# Teensy-Maxuino-Master.net
KiCad netlist of a schematic drawn in EAGLE
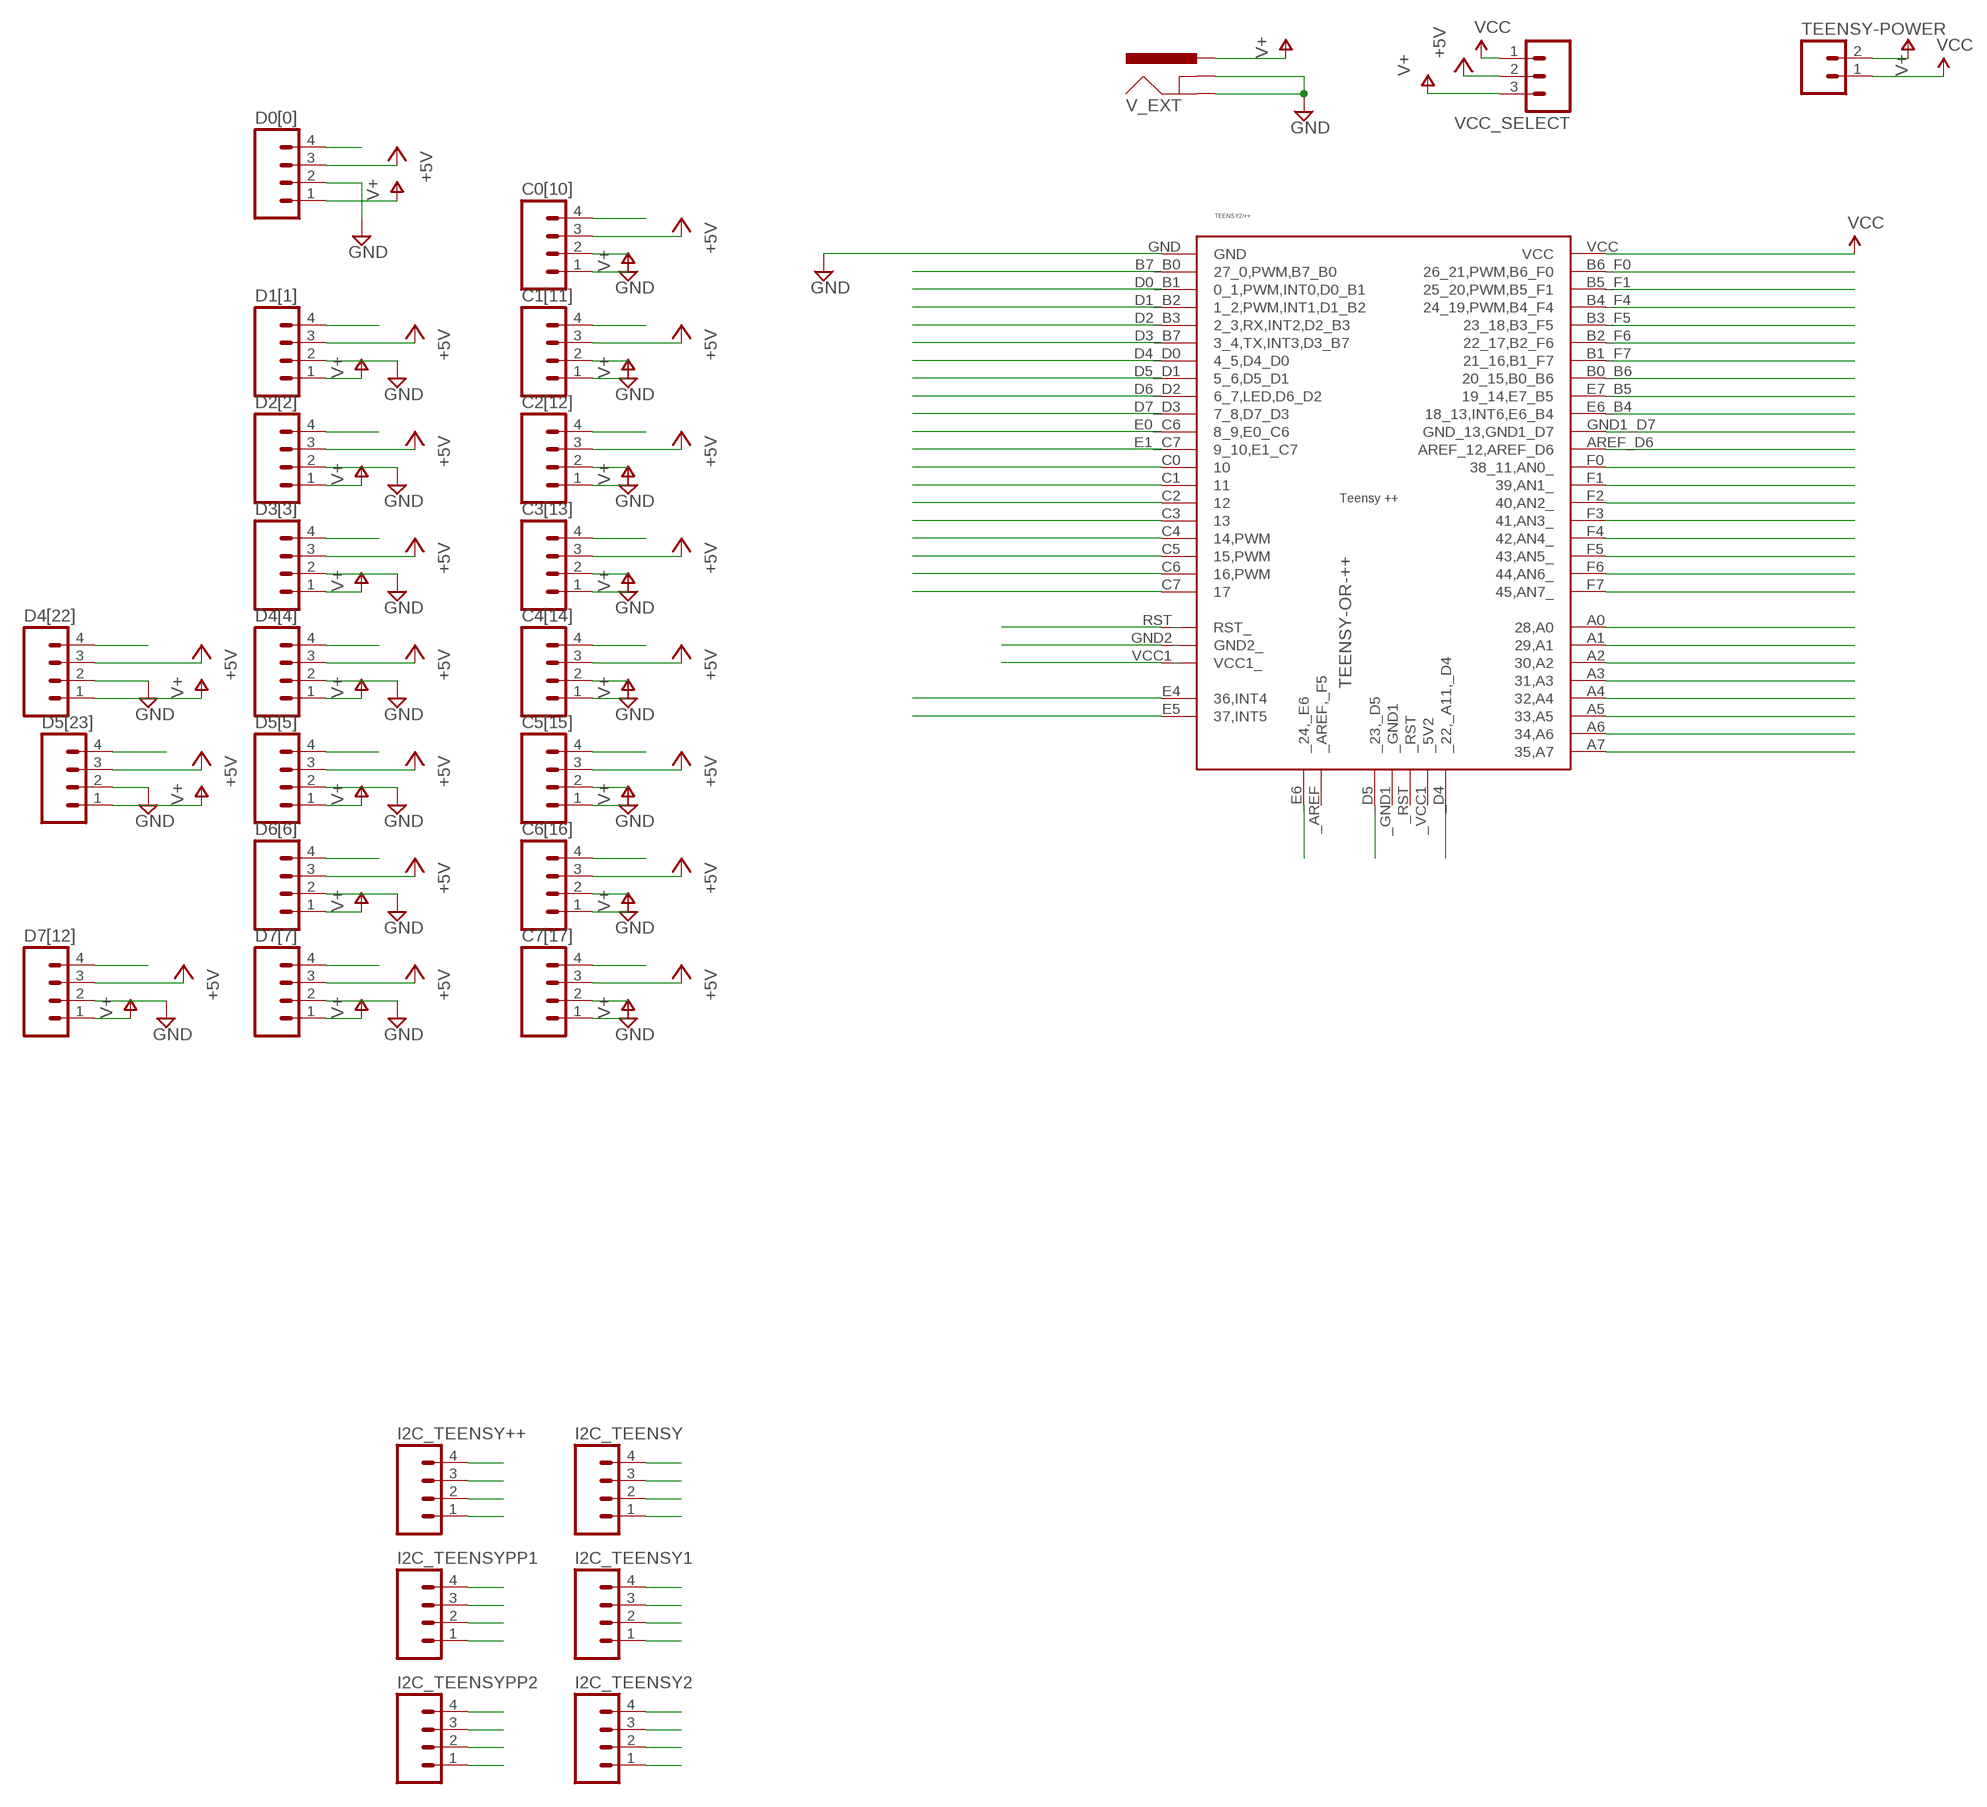
[diagram p0: schematic, sheet 1, part 1 of 2]
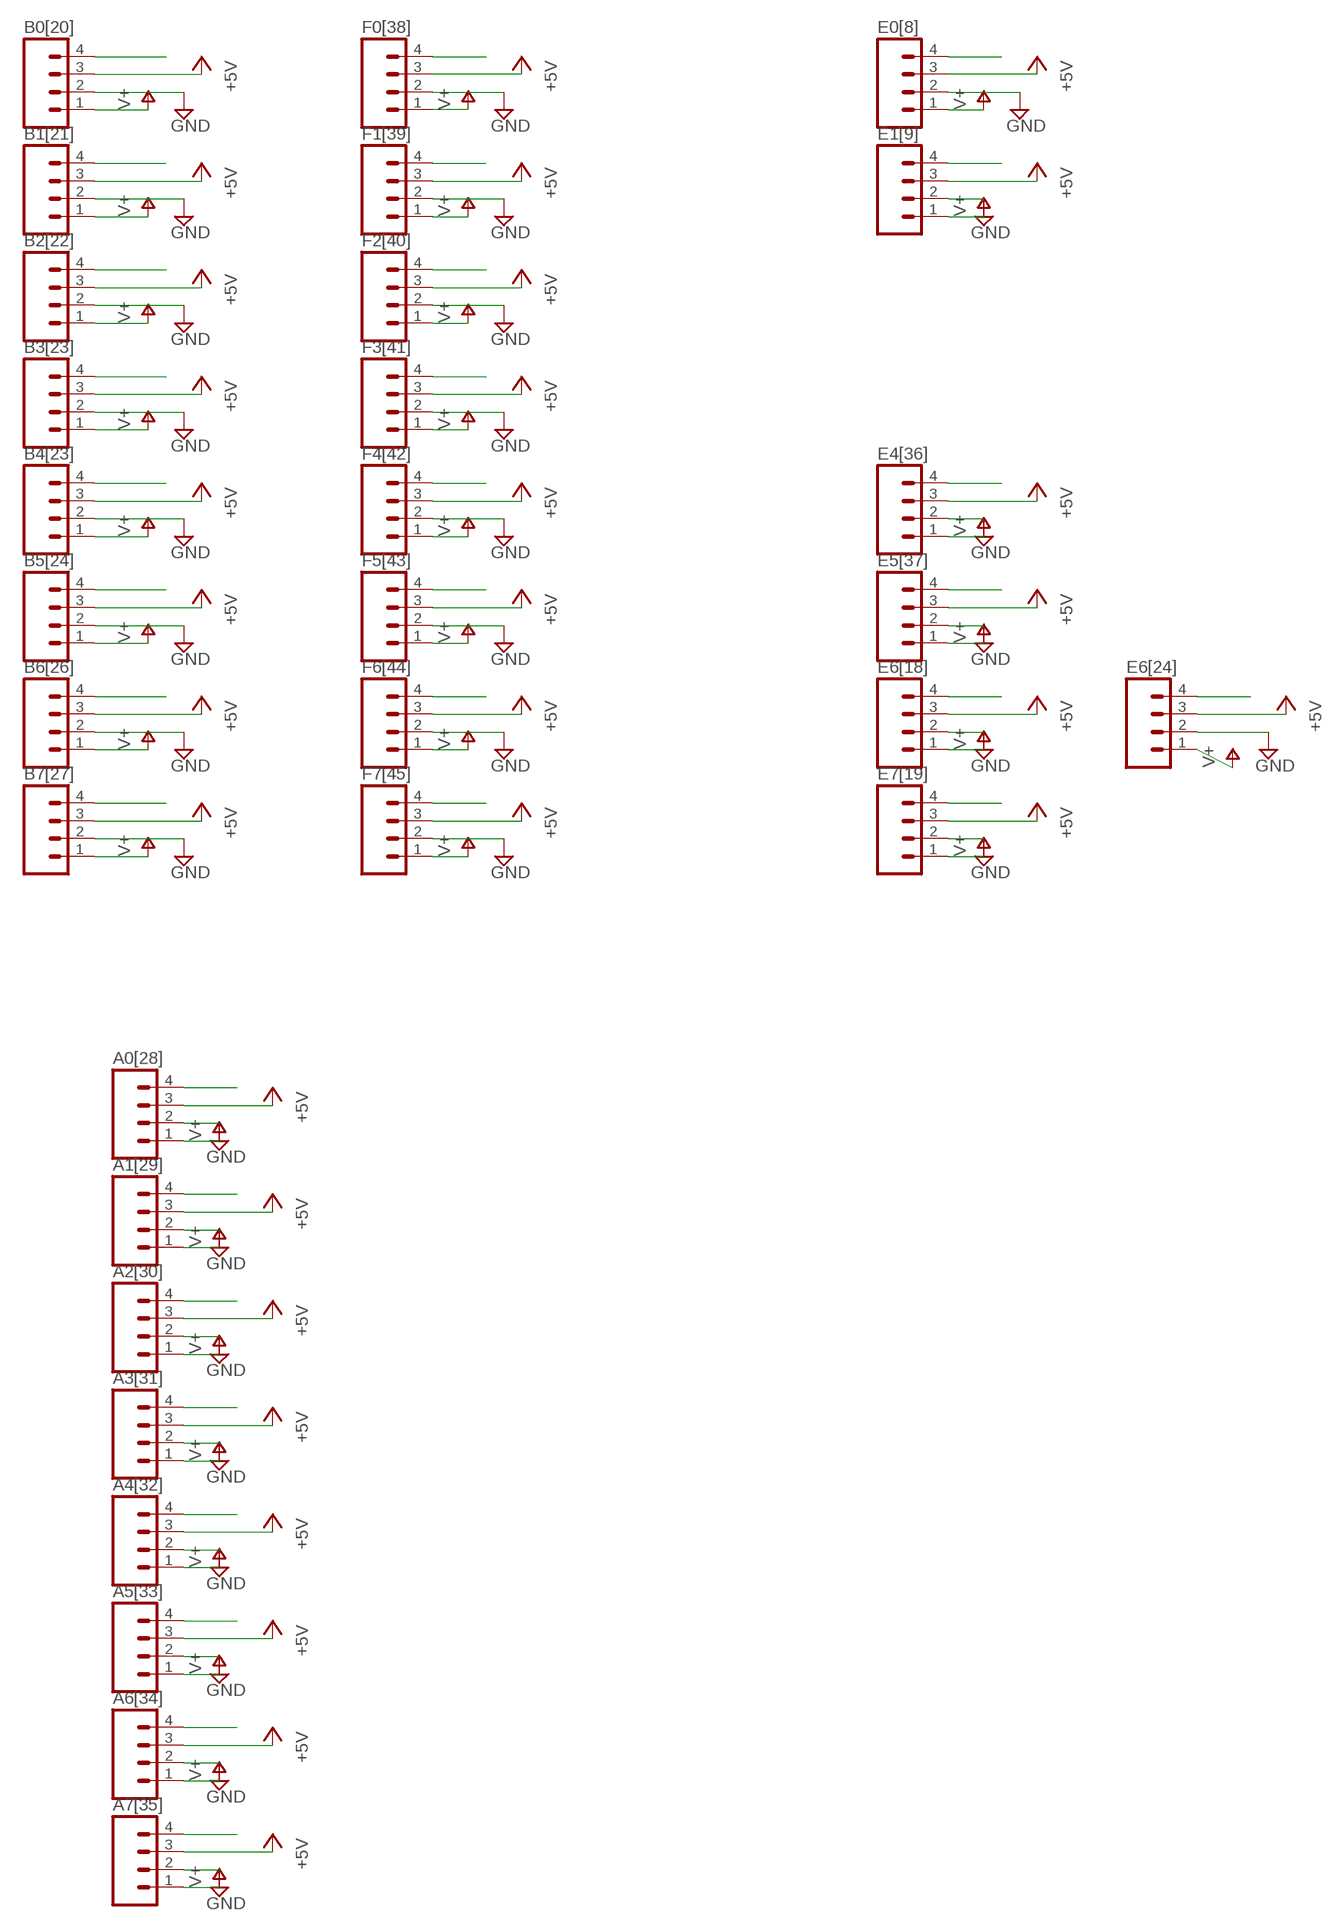
[diagram p1: schematic, sheet 1, part 2 of 2]

(export (version "E")
  (design (tool "Eeschema 10.0.6"))
  (components
    (comp (ref "A0[28]")
      (value "M04PTH")
      (footprint "eagle-import:1X04")
      (libsource (lib "eagle-import") (part "M04PTH"))
    )
    (comp (ref "A1[29]")
      (value "M04PTH")
      (footprint "eagle-import:1X04")
      (libsource (lib "eagle-import") (part "M04PTH"))
    )
    (comp (ref "A2[30]")
      (value "M04PTH")
      (footprint "eagle-import:1X04")
      (libsource (lib "eagle-import") (part "M04PTH"))
    )
    (comp (ref "A3[31]")
      (value "M04PTH")
      (footprint "eagle-import:1X04")
      (libsource (lib "eagle-import") (part "M04PTH"))
    )
    (comp (ref "A4[32]")
      (value "M04PTH")
      (footprint "eagle-import:1X04")
      (libsource (lib "eagle-import") (part "M04PTH"))
    )
    (comp (ref "A5[33]")
      (value "M04PTH")
      (footprint "eagle-import:1X04")
      (libsource (lib "eagle-import") (part "M04PTH"))
    )
    (comp (ref "A6[34]")
      (value "M04PTH")
      (footprint "eagle-import:1X04")
      (libsource (lib "eagle-import") (part "M04PTH"))
    )
    (comp (ref "A7[35]")
      (value "M04PTH")
      (footprint "eagle-import:1X04")
      (libsource (lib "eagle-import") (part "M04PTH"))
    )
    (comp (ref "B0[20]")
      (value "M04PTH")
      (footprint "eagle-import:1X04")
      (libsource (lib "eagle-import") (part "M04PTH"))
    )
    (comp (ref "B1[21]")
      (value "M04PTH")
      (footprint "eagle-import:1X04")
      (libsource (lib "eagle-import") (part "M04PTH"))
    )
    (comp (ref "B2[22]")
      (value "M04PTH")
      (footprint "eagle-import:1X04")
      (libsource (lib "eagle-import") (part "M04PTH"))
    )
    (comp (ref "B3[23]")
      (value "M04PTH")
      (footprint "eagle-import:1X04")
      (libsource (lib "eagle-import") (part "M04PTH"))
    )
    (comp (ref "B4[23]")
      (value "M04PTH")
      (footprint "eagle-import:1X04")
      (libsource (lib "eagle-import") (part "M04PTH"))
    )
    (comp (ref "B5[24]")
      (value "M04PTH")
      (footprint "eagle-import:1X04")
      (libsource (lib "eagle-import") (part "M04PTH"))
    )
    (comp (ref "B6[26]")
      (value "M04PTH")
      (footprint "eagle-import:1X04")
      (libsource (lib "eagle-import") (part "M04PTH"))
    )
    (comp (ref "B7[27]")
      (value "M04PTH")
      (footprint "eagle-import:1X04")
      (libsource (lib "eagle-import") (part "M04PTH"))
    )
    (comp (ref "C0[10]")
      (value "M04PTH")
      (footprint "eagle-import:1X04")
      (libsource (lib "eagle-import") (part "M04PTH"))
    )
    (comp (ref "C1[11]")
      (value "M04PTH")
      (footprint "eagle-import:1X04")
      (libsource (lib "eagle-import") (part "M04PTH"))
    )
    (comp (ref "C2[12]")
      (value "M04PTH")
      (footprint "eagle-import:1X04")
      (libsource (lib "eagle-import") (part "M04PTH"))
    )
    (comp (ref "C3[13]")
      (value "M04PTH")
      (footprint "eagle-import:1X04")
      (libsource (lib "eagle-import") (part "M04PTH"))
    )
    (comp (ref "C4[14]")
      (value "M04PTH")
      (footprint "eagle-import:1X04")
      (libsource (lib "eagle-import") (part "M04PTH"))
    )
    (comp (ref "C5[15]")
      (value "M04PTH")
      (footprint "eagle-import:1X04")
      (libsource (lib "eagle-import") (part "M04PTH"))
    )
    (comp (ref "C6[16]")
      (value "M04PTH")
      (footprint "eagle-import:1X04")
      (libsource (lib "eagle-import") (part "M04PTH"))
    )
    (comp (ref "C7[17]")
      (value "M04PTH")
      (footprint "eagle-import:1X04")
      (libsource (lib "eagle-import") (part "M04PTH"))
    )
    (comp (ref "D0[0]")
      (value "M04PTH")
      (footprint "eagle-import:1X04")
      (libsource (lib "eagle-import") (part "M04PTH"))
    )
    (comp (ref "D1[1]")
      (value "M04PTH")
      (footprint "eagle-import:1X04")
      (libsource (lib "eagle-import") (part "M04PTH"))
    )
    (comp (ref "D2[2]")
      (value "M04PTH")
      (footprint "eagle-import:1X04")
      (libsource (lib "eagle-import") (part "M04PTH"))
    )
    (comp (ref "D3[3]")
      (value "M04PTH")
      (footprint "eagle-import:1X04")
      (libsource (lib "eagle-import") (part "M04PTH"))
    )
    (comp (ref "D4[4]")
      (value "M04PTH")
      (footprint "eagle-import:1X04")
      (libsource (lib "eagle-import") (part "M04PTH"))
    )
    (comp (ref "D4[22]")
      (value "M04PTH")
      (footprint "eagle-import:1X04")
      (libsource (lib "eagle-import") (part "M04PTH"))
    )
    (comp (ref "D5[5]")
      (value "M04PTH")
      (footprint "eagle-import:1X04")
      (libsource (lib "eagle-import") (part "M04PTH"))
    )
    (comp (ref "D5[23]")
      (value "M04PTH")
      (footprint "eagle-import:1X04")
      (libsource (lib "eagle-import") (part "M04PTH"))
    )
    (comp (ref "D6[6]")
      (value "M04PTH")
      (footprint "eagle-import:1X04")
      (libsource (lib "eagle-import") (part "M04PTH"))
    )
    (comp (ref "D7[7]")
      (value "M04PTH")
      (footprint "eagle-import:1X04")
      (libsource (lib "eagle-import") (part "M04PTH"))
    )
    (comp (ref "D7[12]")
      (value "M04PTH")
      (footprint "eagle-import:1X04")
      (libsource (lib "eagle-import") (part "M04PTH"))
    )
    (comp (ref "E0[8]")
      (value "M04PTH")
      (footprint "eagle-import:1X04")
      (libsource (lib "eagle-import") (part "M04PTH"))
    )
    (comp (ref "E1[9]")
      (value "M04PTH")
      (footprint "eagle-import:1X04")
      (libsource (lib "eagle-import") (part "M04PTH"))
    )
    (comp (ref "E4[36]")
      (value "M04PTH")
      (footprint "eagle-import:1X04")
      (libsource (lib "eagle-import") (part "M04PTH"))
    )
    (comp (ref "E5[37]")
      (value "M04PTH")
      (footprint "eagle-import:1X04")
      (libsource (lib "eagle-import") (part "M04PTH"))
    )
    (comp (ref "E6[18]")
      (value "M04PTH")
      (footprint "eagle-import:1X04")
      (libsource (lib "eagle-import") (part "M04PTH"))
    )
    (comp (ref "E6[24]")
      (value "M04PTH")
      (footprint "eagle-import:1X04")
      (libsource (lib "eagle-import") (part "M04PTH"))
    )
    (comp (ref "E7[19]")
      (value "M04PTH")
      (footprint "eagle-import:1X04")
      (libsource (lib "eagle-import") (part "M04PTH"))
    )
    (comp (ref "F0[38]")
      (value "M04PTH")
      (footprint "eagle-import:1X04")
      (libsource (lib "eagle-import") (part "M04PTH"))
    )
    (comp (ref "F1[39]")
      (value "M04PTH")
      (footprint "eagle-import:1X04")
      (libsource (lib "eagle-import") (part "M04PTH"))
    )
    (comp (ref "F2[40]")
      (value "M04PTH")
      (footprint "eagle-import:1X04")
      (libsource (lib "eagle-import") (part "M04PTH"))
    )
    (comp (ref "F3[41]")
      (value "M04PTH")
      (footprint "eagle-import:1X04")
      (libsource (lib "eagle-import") (part "M04PTH"))
    )
    (comp (ref "F4[42]")
      (value "M04PTH")
      (footprint "eagle-import:1X04")
      (libsource (lib "eagle-import") (part "M04PTH"))
    )
    (comp (ref "F5[43]")
      (value "M04PTH")
      (footprint "eagle-import:1X04")
      (libsource (lib "eagle-import") (part "M04PTH"))
    )
    (comp (ref "F6[44]")
      (value "M04PTH")
      (footprint "eagle-import:1X04")
      (libsource (lib "eagle-import") (part "M04PTH"))
    )
    (comp (ref "F7[45]")
      (value "M04PTH")
      (footprint "eagle-import:1X04")
      (libsource (lib "eagle-import") (part "M04PTH"))
    )
    (comp (ref "I2C_TEENSY")
      (value "M04PTH")
      (footprint "eagle-import:1X04")
      (libsource (lib "eagle-import") (part "M04PTH"))
    )
    (comp (ref "I2C_TEENSY++")
      (value "M04PTH")
      (footprint "eagle-import:1X04")
      (libsource (lib "eagle-import") (part "M04PTH"))
    )
    (comp (ref "I2C_TEENSY1")
      (value "M04PTH")
      (footprint "eagle-import:1X04")
      (libsource (lib "eagle-import") (part "M04PTH"))
    )
    (comp (ref "I2C_TEENSY2")
      (value "M04PTH")
      (footprint "eagle-import:1X04")
      (libsource (lib "eagle-import") (part "M04PTH"))
    )
    (comp (ref "I2C_TEENSYPP1")
      (value "M04PTH")
      (footprint "eagle-import:1X04")
      (libsource (lib "eagle-import") (part "M04PTH"))
    )
    (comp (ref "I2C_TEENSYPP2")
      (value "M04PTH")
      (footprint "eagle-import:1X04")
      (libsource (lib "eagle-import") (part "M04PTH"))
    )
    (comp (ref "TEENSY-POWER")
      (value "M02PTH")
      (footprint "eagle-import:1X02")
      (libsource (lib "eagle-import") (part "M02PTH"))
    )
    (comp (ref "TEENSY2/++")
      (value "TEENSY-OR-++")
      (footprint "eagle-import:TEENSY-OR-++")
      (libsource (lib "eagle-import") (part "TEENSY-OR-++"))
    )
    (comp (ref "VCC_SELECT")
      (value "M03PTH")
      (footprint "eagle-import:1X03")
      (libsource (lib "eagle-import") (part "M03PTH"))
    )
    (comp (ref "V_EXT")
      (value "POWER_JACKPTH")
      (footprint "eagle-import:POWER_JACK_PTH")
      (libsource (lib "eagle-import") (part "POWER_JACKPTH"))
    )
  )
  (nets
    (net (code "1") (name "+5V") (class "Default")
      (node (ref "A0[28]") (pin "3") (pinfunction "3_3") (pintype "passive"))
      (node (ref "A1[29]") (pin "3") (pinfunction "3_3") (pintype "passive"))
      (node (ref "A2[30]") (pin "3") (pinfunction "3_3") (pintype "passive"))
      (node (ref "A3[31]") (pin "3") (pinfunction "3_3") (pintype "passive"))
      (node (ref "A4[32]") (pin "3") (pinfunction "3_3") (pintype "passive"))
      (node (ref "A5[33]") (pin "3") (pinfunction "3_3") (pintype "passive"))
      (node (ref "A6[34]") (pin "3") (pinfunction "3_3") (pintype "passive"))
      (node (ref "A7[35]") (pin "3") (pinfunction "3_3") (pintype "passive"))
      (node (ref "B0[20]") (pin "3") (pinfunction "3_3") (pintype "passive"))
      (node (ref "B1[21]") (pin "3") (pinfunction "3_3") (pintype "passive"))
      (node (ref "B2[22]") (pin "3") (pinfunction "3_3") (pintype "passive"))
      (node (ref "B3[23]") (pin "3") (pinfunction "3_3") (pintype "passive"))
      (node (ref "B4[23]") (pin "3") (pinfunction "3_3") (pintype "passive"))
      (node (ref "B5[24]") (pin "3") (pinfunction "3_3") (pintype "passive"))
      (node (ref "B6[26]") (pin "3") (pinfunction "3_3") (pintype "passive"))
      (node (ref "B7[27]") (pin "3") (pinfunction "3_3") (pintype "passive"))
      (node (ref "C0[10]") (pin "3") (pinfunction "3_3") (pintype "passive"))
      (node (ref "C1[11]") (pin "3") (pinfunction "3_3") (pintype "passive"))
      (node (ref "C2[12]") (pin "3") (pinfunction "3_3") (pintype "passive"))
      (node (ref "C3[13]") (pin "3") (pinfunction "3_3") (pintype "passive"))
      (node (ref "C4[14]") (pin "3") (pinfunction "3_3") (pintype "passive"))
      (node (ref "C5[15]") (pin "3") (pinfunction "3_3") (pintype "passive"))
      (node (ref "C6[16]") (pin "3") (pinfunction "3_3") (pintype "passive"))
      (node (ref "C7[17]") (pin "3") (pinfunction "3_3") (pintype "passive"))
      (node (ref "D0[0]") (pin "3") (pinfunction "3_3") (pintype "passive"))
      (node (ref "D1[1]") (pin "3") (pinfunction "3_3") (pintype "passive"))
      (node (ref "D2[2]") (pin "3") (pinfunction "3_3") (pintype "passive"))
      (node (ref "D3[3]") (pin "3") (pinfunction "3_3") (pintype "passive"))
      (node (ref "D4[22]") (pin "3") (pinfunction "3_3") (pintype "passive"))
      (node (ref "D4[4]") (pin "3") (pinfunction "3_3") (pintype "passive"))
      (node (ref "D5[23]") (pin "3") (pinfunction "3_3") (pintype "passive"))
      (node (ref "D5[5]") (pin "3") (pinfunction "3_3") (pintype "passive"))
      (node (ref "D6[6]") (pin "3") (pinfunction "3_3") (pintype "passive"))
      (node (ref "D7[12]") (pin "3") (pinfunction "3_3") (pintype "passive"))
      (node (ref "D7[7]") (pin "3") (pinfunction "3_3") (pintype "passive"))
      (node (ref "E0[8]") (pin "3") (pinfunction "3_3") (pintype "passive"))
      (node (ref "E1[9]") (pin "3") (pinfunction "3_3") (pintype "passive"))
      (node (ref "E4[36]") (pin "3") (pinfunction "3_3") (pintype "passive"))
      (node (ref "E5[37]") (pin "3") (pinfunction "3_3") (pintype "passive"))
      (node (ref "E6[18]") (pin "3") (pinfunction "3_3") (pintype "passive"))
      (node (ref "E6[24]") (pin "3") (pinfunction "3_3") (pintype "passive"))
      (node (ref "E7[19]") (pin "3") (pinfunction "3_3") (pintype "passive"))
      (node (ref "F0[38]") (pin "3") (pinfunction "3_3") (pintype "passive"))
      (node (ref "F1[39]") (pin "3") (pinfunction "3_3") (pintype "passive"))
      (node (ref "F2[40]") (pin "3") (pinfunction "3_3") (pintype "passive"))
      (node (ref "F3[41]") (pin "3") (pinfunction "3_3") (pintype "passive"))
      (node (ref "F4[42]") (pin "3") (pinfunction "3_3") (pintype "passive"))
      (node (ref "F5[43]") (pin "3") (pinfunction "3_3") (pintype "passive"))
      (node (ref "F6[44]") (pin "3") (pinfunction "3_3") (pintype "passive"))
      (node (ref "F7[45]") (pin "3") (pinfunction "3_3") (pintype "passive"))
      (node (ref "VCC_SELECT") (pin "2") (pinfunction "2_2") (pintype "passive"))
    )
    (net (code "2") (name "/A0") (class "Default")
      (node (ref "A0[28]") (pin "4") (pinfunction "4_4") (pintype "passive"))
      (node (ref "TEENSY2/++") (pin "A0") (pinfunction "28,A0_A0") (pintype "bidirectional"))
    )
    (net (code "3") (name "/A1") (class "Default")
      (node (ref "A1[29]") (pin "4") (pinfunction "4_4") (pintype "passive"))
      (node (ref "TEENSY2/++") (pin "A1") (pinfunction "29,A1_A1") (pintype "bidirectional"))
    )
    (net (code "4") (name "/A2") (class "Default")
      (node (ref "A2[30]") (pin "4") (pinfunction "4_4") (pintype "passive"))
      (node (ref "TEENSY2/++") (pin "A2") (pinfunction "30,A2_A2") (pintype "bidirectional"))
    )
    (net (code "5") (name "/A3") (class "Default")
      (node (ref "A3[31]") (pin "4") (pinfunction "4_4") (pintype "passive"))
      (node (ref "TEENSY2/++") (pin "A3") (pinfunction "31,A3_A3") (pintype "bidirectional"))
    )
    (net (code "6") (name "/A4") (class "Default")
      (node (ref "A4[32]") (pin "4") (pinfunction "4_4") (pintype "passive"))
      (node (ref "TEENSY2/++") (pin "A4") (pinfunction "32,A4_A4") (pintype "bidirectional"))
    )
    (net (code "7") (name "/A5") (class "Default")
      (node (ref "A5[33]") (pin "4") (pinfunction "4_4") (pintype "passive"))
      (node (ref "TEENSY2/++") (pin "A5") (pinfunction "33,A5_A5") (pintype "bidirectional"))
    )
    (net (code "8") (name "/A6") (class "Default")
      (node (ref "A6[34]") (pin "4") (pinfunction "4_4") (pintype "passive"))
      (node (ref "TEENSY2/++") (pin "A6") (pinfunction "34,A6_A6") (pintype "bidirectional"))
    )
    (net (code "9") (name "/A7") (class "Default")
      (node (ref "A7[35]") (pin "4") (pinfunction "4_4") (pintype "passive"))
      (node (ref "TEENSY2/++") (pin "A7") (pinfunction "35,A7_A7") (pintype "bidirectional"))
    )
    (net (code "10") (name "/B0_B6") (class "Default")
      (node (ref "B0[20]") (pin "4") (pinfunction "4_4") (pintype "passive"))
      (node (ref "TEENSY2/++") (pin "B0_B6") (pinfunction "20_15,B0_B6_B0_B6") (pintype "bidirectional"))
    )
    (net (code "11") (name "/B1_F7") (class "Default")
      (node (ref "B1[21]") (pin "4") (pinfunction "4_4") (pintype "passive"))
      (node (ref "TEENSY2/++") (pin "B1_F7") (pinfunction "21_16,B1_F7_B1_F7") (pintype "bidirectional"))
    )
    (net (code "12") (name "/B2_F6") (class "Default")
      (node (ref "B2[22]") (pin "4") (pinfunction "4_4") (pintype "passive"))
      (node (ref "TEENSY2/++") (pin "B2_F6") (pinfunction "22_17,B2_F6_B2_F6") (pintype "bidirectional"))
    )
    (net (code "13") (name "/B3_F5") (class "Default")
      (node (ref "B3[23]") (pin "4") (pinfunction "4_4") (pintype "passive"))
      (node (ref "TEENSY2/++") (pin "B3_F5") (pinfunction "23_18,B3_F5_B3_F5") (pintype "bidirectional"))
    )
    (net (code "14") (name "/B4_F4") (class "Default")
      (node (ref "B4[23]") (pin "4") (pinfunction "4_4") (pintype "passive"))
      (node (ref "TEENSY2/++") (pin "B4_F4") (pinfunction "24_19,PWM,B4_F4_B4_F4") (pintype "bidirectional"))
    )
    (net (code "15") (name "/B5_F1") (class "Default")
      (node (ref "B5[24]") (pin "4") (pinfunction "4_4") (pintype "passive"))
      (node (ref "TEENSY2/++") (pin "B5_F1") (pinfunction "25_20,PWM,B5_F1_B5_F1") (pintype "bidirectional"))
    )
    (net (code "16") (name "/B6_F0") (class "Default")
      (node (ref "B6[26]") (pin "4") (pinfunction "4_4") (pintype "passive"))
      (node (ref "TEENSY2/++") (pin "B6_F0") (pinfunction "26_21,PWM,B6_F0_B6_F0") (pintype "bidirectional"))
    )
    (net (code "17") (name "/B7_B0") (class "Default")
      (node (ref "B7[27]") (pin "4") (pinfunction "4_4") (pintype "passive"))
      (node (ref "TEENSY2/++") (pin "B7_B0") (pinfunction "27_0,PWM,B7_B0_B7_B0") (pintype "bidirectional"))
    )
    (net (code "18") (name "/C0") (class "Default")
      (node (ref "C0[10]") (pin "4") (pinfunction "4_4") (pintype "passive"))
      (node (ref "TEENSY2/++") (pin "C0") (pinfunction "10_C0") (pintype "bidirectional"))
    )
    (net (code "19") (name "/C1") (class "Default")
      (node (ref "C1[11]") (pin "4") (pinfunction "4_4") (pintype "passive"))
      (node (ref "TEENSY2/++") (pin "C1") (pinfunction "11_C1") (pintype "bidirectional"))
    )
    (net (code "20") (name "/C2") (class "Default")
      (node (ref "C2[12]") (pin "4") (pinfunction "4_4") (pintype "passive"))
      (node (ref "TEENSY2/++") (pin "C2") (pinfunction "12_C2") (pintype "bidirectional"))
    )
    (net (code "21") (name "/C3") (class "Default")
      (node (ref "C3[13]") (pin "4") (pinfunction "4_4") (pintype "passive"))
      (node (ref "TEENSY2/++") (pin "C3") (pinfunction "13_C3") (pintype "bidirectional"))
    )
    (net (code "22") (name "/C4") (class "Default")
      (node (ref "C4[14]") (pin "4") (pinfunction "4_4") (pintype "passive"))
      (node (ref "TEENSY2/++") (pin "C4") (pinfunction "14,PWM_C4") (pintype "bidirectional"))
    )
    (net (code "23") (name "/C5") (class "Default")
      (node (ref "C5[15]") (pin "4") (pinfunction "4_4") (pintype "passive"))
      (node (ref "TEENSY2/++") (pin "C5") (pinfunction "15,PWM_C5") (pintype "bidirectional"))
    )
    (net (code "24") (name "/C6") (class "Default")
      (node (ref "C6[16]") (pin "4") (pinfunction "4_4") (pintype "passive"))
      (node (ref "TEENSY2/++") (pin "C6") (pinfunction "16,PWM_C6") (pintype "bidirectional"))
    )
    (net (code "25") (name "/C7") (class "Default")
      (node (ref "C7[17]") (pin "4") (pinfunction "4_4") (pintype "passive"))
      (node (ref "TEENSY2/++") (pin "C7") (pinfunction "17_C7") (pintype "bidirectional"))
    )
    (net (code "26") (name "/D0_B1") (class "Default")
      (node (ref "D0[0]") (pin "4") (pinfunction "4_4") (pintype "passive"))
      (node (ref "I2C_TEENSY++") (pin "4") (pinfunction "4_4") (pintype "passive"))
      (node (ref "I2C_TEENSYPP1") (pin "4") (pinfunction "4_4") (pintype "passive"))
      (node (ref "I2C_TEENSYPP2") (pin "4") (pinfunction "4_4") (pintype "passive"))
      (node (ref "TEENSY2/++") (pin "D0_B1") (pinfunction "0_1,PWM,INT0,D0_B1_D0_B1") (pintype "bidirectional"))
    )
    (net (code "27") (name "/D1_B2") (class "Default")
      (node (ref "D1[1]") (pin "4") (pinfunction "4_4") (pintype "passive"))
      (node (ref "I2C_TEENSY++") (pin "3") (pinfunction "3_3") (pintype "passive"))
      (node (ref "I2C_TEENSYPP1") (pin "3") (pinfunction "3_3") (pintype "passive"))
      (node (ref "I2C_TEENSYPP2") (pin "3") (pinfunction "3_3") (pintype "passive"))
      (node (ref "TEENSY2/++") (pin "D1_B2") (pinfunction "1_2,PWM,INT1,D1_B2_D1_B2") (pintype "bidirectional"))
    )
    (net (code "28") (name "/D2_B3") (class "Default")
      (node (ref "D2[2]") (pin "4") (pinfunction "4_4") (pintype "passive"))
      (node (ref "TEENSY2/++") (pin "D2_B3") (pinfunction "2_3,RX,INT2,D2_B3_D2_B3") (pintype "bidirectional"))
    )
    (net (code "29") (name "/D3_B7") (class "Default")
      (node (ref "D3[3]") (pin "4") (pinfunction "4_4") (pintype "passive"))
      (node (ref "TEENSY2/++") (pin "D3_B7") (pinfunction "3_4,TX,INT3,D3_B7_D3_B7") (pintype "bidirectional"))
    )
    (net (code "30") (name "/D4_D0") (class "Default")
      (node (ref "D4[4]") (pin "4") (pinfunction "4_4") (pintype "passive"))
      (node (ref "I2C_TEENSY") (pin "4") (pinfunction "4_4") (pintype "passive"))
      (node (ref "I2C_TEENSY1") (pin "4") (pinfunction "4_4") (pintype "passive"))
      (node (ref "I2C_TEENSY2") (pin "4") (pinfunction "4_4") (pintype "passive"))
      (node (ref "TEENSY2/++") (pin "D4_D0") (pinfunction "4_5,D4_D0_D4_D0") (pintype "bidirectional"))
    )
    (net (code "31") (name "/D5_D1") (class "Default")
      (node (ref "D5[5]") (pin "4") (pinfunction "4_4") (pintype "passive"))
      (node (ref "I2C_TEENSY") (pin "3") (pinfunction "3_3") (pintype "passive"))
      (node (ref "I2C_TEENSY1") (pin "3") (pinfunction "3_3") (pintype "passive"))
      (node (ref "I2C_TEENSY2") (pin "3") (pinfunction "3_3") (pintype "passive"))
      (node (ref "TEENSY2/++") (pin "D5_D1") (pinfunction "5_6,D5_D1_D5_D1") (pintype "bidirectional"))
    )
    (net (code "32") (name "/D6_D2") (class "Default")
      (node (ref "D6[6]") (pin "4") (pinfunction "4_4") (pintype "passive"))
      (node (ref "TEENSY2/++") (pin "D6_D2") (pinfunction "6_7,LED,D6_D2_D6_D2") (pintype "bidirectional"))
    )
    (net (code "33") (name "/D7_D3") (class "Default")
      (node (ref "D7[7]") (pin "4") (pinfunction "4_4") (pintype "passive"))
      (node (ref "TEENSY2/++") (pin "D7_D3") (pinfunction "7_8,D7_D3_D7_D3") (pintype "bidirectional"))
    )
    (net (code "34") (name "/E0_C6") (class "Default")
      (node (ref "E0[8]") (pin "4") (pinfunction "4_4") (pintype "passive"))
      (node (ref "TEENSY2/++") (pin "E0_C6") (pinfunction "8_9,E0_C6_E0_C6") (pintype "bidirectional"))
    )
    (net (code "35") (name "/E1_C7") (class "Default")
      (node (ref "E1[9]") (pin "4") (pinfunction "4_4") (pintype "passive"))
      (node (ref "TEENSY2/++") (pin "E1_C7") (pinfunction "9_10,E1_C7_E1_C7") (pintype "bidirectional"))
    )
    (net (code "36") (name "/E4") (class "Default")
      (node (ref "E4[36]") (pin "4") (pinfunction "4_4") (pintype "passive"))
      (node (ref "TEENSY2/++") (pin "E4") (pinfunction "36,INT4_E4") (pintype "bidirectional"))
    )
    (net (code "37") (name "/E5") (class "Default")
      (node (ref "E5[37]") (pin "4") (pinfunction "4_4") (pintype "passive"))
      (node (ref "TEENSY2/++") (pin "E5") (pinfunction "37,INT5_E5") (pintype "bidirectional"))
    )
    (net (code "38") (name "/E6_B4") (class "Default")
      (node (ref "E6[18]") (pin "4") (pinfunction "4_4") (pintype "passive"))
      (node (ref "TEENSY2/++") (pin "E6_B4") (pinfunction "18_13,INT6,E6_B4_E6_B4") (pintype "bidirectional"))
    )
    (net (code "39") (name "/E7_B5") (class "Default")
      (node (ref "E7[19]") (pin "4") (pinfunction "4_4") (pintype "passive"))
      (node (ref "TEENSY2/++") (pin "E7_B5") (pinfunction "19_14,E7_B5_E7_B5") (pintype "bidirectional"))
    )
    (net (code "40") (name "/F0") (class "Default")
      (node (ref "F0[38]") (pin "4") (pinfunction "4_4") (pintype "passive"))
      (node (ref "TEENSY2/++") (pin "F0") (pinfunction "38_11,AN0__F0") (pintype "bidirectional"))
    )
    (net (code "41") (name "/F1") (class "Default")
      (node (ref "F1[39]") (pin "4") (pinfunction "4_4") (pintype "passive"))
      (node (ref "TEENSY2/++") (pin "F1") (pinfunction "39,AN1__F1") (pintype "bidirectional"))
    )
    (net (code "42") (name "/F2") (class "Default")
      (node (ref "F2[40]") (pin "4") (pinfunction "4_4") (pintype "passive"))
      (node (ref "TEENSY2/++") (pin "F2") (pinfunction "40,AN2__F2") (pintype "bidirectional"))
    )
    (net (code "43") (name "/F3") (class "Default")
      (node (ref "F3[41]") (pin "4") (pinfunction "4_4") (pintype "passive"))
      (node (ref "TEENSY2/++") (pin "F3") (pinfunction "41,AN3__F3") (pintype "bidirectional"))
    )
    (net (code "44") (name "/F4") (class "Default")
      (node (ref "F4[42]") (pin "4") (pinfunction "4_4") (pintype "passive"))
      (node (ref "TEENSY2/++") (pin "F4") (pinfunction "42,AN4__F4") (pintype "bidirectional"))
    )
    (net (code "45") (name "/F5") (class "Default")
      (node (ref "F5[43]") (pin "4") (pinfunction "4_4") (pintype "passive"))
      (node (ref "TEENSY2/++") (pin "F5") (pinfunction "43,AN5__F5") (pintype "bidirectional"))
    )
    (net (code "46") (name "/F6") (class "Default")
      (node (ref "F6[44]") (pin "4") (pinfunction "4_4") (pintype "passive"))
      (node (ref "TEENSY2/++") (pin "F6") (pinfunction "44,AN6__F6") (pintype "bidirectional"))
    )
    (net (code "47") (name "/F7") (class "Default")
      (node (ref "F7[45]") (pin "4") (pinfunction "4_4") (pintype "passive"))
      (node (ref "TEENSY2/++") (pin "F7") (pinfunction "45,AN7__F7") (pintype "bidirectional"))
    )
    (net (code "48") (name "/GND1_D7") (class "Default")
      (node (ref "D7[12]") (pin "4") (pinfunction "4_4") (pintype "passive"))
      (node (ref "TEENSY2/++") (pin "GND1_D7") (pinfunction "GND_13,GND1_D7_GND1_D7") (pintype "power_in"))
    )
    (net (code "49") (name "/_D4") (class "Default")
      (node (ref "D4[22]") (pin "4") (pinfunction "4_4") (pintype "passive"))
      (node (ref "TEENSY2/++") (pin "_D4") (pinfunction "_22,_A11,_D4__D4") (pintype "bidirectional"))
    )
    (net (code "50") (name "/_D5") (class "Default")
      (node (ref "D5[23]") (pin "4") (pinfunction "4_4") (pintype "passive"))
      (node (ref "TEENSY2/++") (pin "_D5") (pinfunction "_23,_D5__D5") (pintype "bidirectional"))
    )
    (net (code "51") (name "/_E6") (class "Default")
      (node (ref "E6[24]") (pin "4") (pinfunction "4_4") (pintype "passive"))
      (node (ref "TEENSY2/++") (pin "_E6") (pinfunction "_24,_E6__E6") (pintype "bidirectional"))
    )
    (net (code "52") (name "GND") (class "Default")
      (node (ref "A0[28]") (pin "2") (pinfunction "2_2") (pintype "passive"))
      (node (ref "A1[29]") (pin "2") (pinfunction "2_2") (pintype "passive"))
      (node (ref "A2[30]") (pin "2") (pinfunction "2_2") (pintype "passive"))
      (node (ref "A3[31]") (pin "2") (pinfunction "2_2") (pintype "passive"))
      (node (ref "A4[32]") (pin "2") (pinfunction "2_2") (pintype "passive"))
      (node (ref "A5[33]") (pin "2") (pinfunction "2_2") (pintype "passive"))
      (node (ref "A6[34]") (pin "2") (pinfunction "2_2") (pintype "passive"))
      (node (ref "A7[35]") (pin "2") (pinfunction "2_2") (pintype "passive"))
      (node (ref "B0[20]") (pin "2") (pinfunction "2_2") (pintype "passive"))
      (node (ref "B1[21]") (pin "2") (pinfunction "2_2") (pintype "passive"))
      (node (ref "B2[22]") (pin "2") (pinfunction "2_2") (pintype "passive"))
      (node (ref "B3[23]") (pin "2") (pinfunction "2_2") (pintype "passive"))
      (node (ref "B4[23]") (pin "2") (pinfunction "2_2") (pintype "passive"))
      (node (ref "B5[24]") (pin "2") (pinfunction "2_2") (pintype "passive"))
      (node (ref "B6[26]") (pin "2") (pinfunction "2_2") (pintype "passive"))
      (node (ref "B7[27]") (pin "2") (pinfunction "2_2") (pintype "passive"))
      (node (ref "C0[10]") (pin "2") (pinfunction "2_2") (pintype "passive"))
      (node (ref "C1[11]") (pin "2") (pinfunction "2_2") (pintype "passive"))
      (node (ref "C2[12]") (pin "2") (pinfunction "2_2") (pintype "passive"))
      (node (ref "C3[13]") (pin "2") (pinfunction "2_2") (pintype "passive"))
      (node (ref "C4[14]") (pin "2") (pinfunction "2_2") (pintype "passive"))
      (node (ref "C5[15]") (pin "2") (pinfunction "2_2") (pintype "passive"))
      (node (ref "C6[16]") (pin "2") (pinfunction "2_2") (pintype "passive"))
      (node (ref "C7[17]") (pin "2") (pinfunction "2_2") (pintype "passive"))
      (node (ref "D0[0]") (pin "2") (pinfunction "2_2") (pintype "passive"))
      (node (ref "D1[1]") (pin "2") (pinfunction "2_2") (pintype "passive"))
      (node (ref "D2[2]") (pin "2") (pinfunction "2_2") (pintype "passive"))
      (node (ref "D3[3]") (pin "2") (pinfunction "2_2") (pintype "passive"))
      (node (ref "D4[22]") (pin "2") (pinfunction "2_2") (pintype "passive"))
      (node (ref "D4[4]") (pin "2") (pinfunction "2_2") (pintype "passive"))
      (node (ref "D5[23]") (pin "2") (pinfunction "2_2") (pintype "passive"))
      (node (ref "D5[5]") (pin "2") (pinfunction "2_2") (pintype "passive"))
      (node (ref "D6[6]") (pin "2") (pinfunction "2_2") (pintype "passive"))
      (node (ref "D7[12]") (pin "2") (pinfunction "2_2") (pintype "passive"))
      (node (ref "D7[7]") (pin "2") (pinfunction "2_2") (pintype "passive"))
      (node (ref "E0[8]") (pin "2") (pinfunction "2_2") (pintype "passive"))
      (node (ref "E1[9]") (pin "2") (pinfunction "2_2") (pintype "passive"))
      (node (ref "E4[36]") (pin "2") (pinfunction "2_2") (pintype "passive"))
      (node (ref "E5[37]") (pin "2") (pinfunction "2_2") (pintype "passive"))
      (node (ref "E6[18]") (pin "2") (pinfunction "2_2") (pintype "passive"))
      (node (ref "E6[24]") (pin "2") (pinfunction "2_2") (pintype "passive"))
      (node (ref "E7[19]") (pin "2") (pinfunction "2_2") (pintype "passive"))
      (node (ref "F0[38]") (pin "2") (pinfunction "2_2") (pintype "passive"))
      (node (ref "F1[39]") (pin "2") (pinfunction "2_2") (pintype "passive"))
      (node (ref "F2[40]") (pin "2") (pinfunction "2_2") (pintype "passive"))
      (node (ref "F3[41]") (pin "2") (pinfunction "2_2") (pintype "passive"))
      (node (ref "F4[42]") (pin "2") (pinfunction "2_2") (pintype "passive"))
      (node (ref "F5[43]") (pin "2") (pinfunction "2_2") (pintype "passive"))
      (node (ref "F6[44]") (pin "2") (pinfunction "2_2") (pintype "passive"))
      (node (ref "F7[45]") (pin "2") (pinfunction "2_2") (pintype "passive"))
      (node (ref "I2C_TEENSY") (pin "1") (pinfunction "1_1") (pintype "passive"))
      (node (ref "I2C_TEENSY++") (pin "1") (pinfunction "1_1") (pintype "passive"))
      (node (ref "I2C_TEENSY1") (pin "1") (pinfunction "1_1") (pintype "passive"))
      (node (ref "I2C_TEENSY2") (pin "1") (pinfunction "1_1") (pintype "passive"))
      (node (ref "I2C_TEENSYPP1") (pin "1") (pinfunction "1_1") (pintype "passive"))
      (node (ref "I2C_TEENSYPP2") (pin "1") (pinfunction "1_1") (pintype "passive"))
      (node (ref "TEENSY2/++") (pin "GND") (pinfunction "GND_GND") (pintype "power_in"))
      (node (ref "V_EXT") (pin "GND") (pinfunction "GND_GND") (pintype "bidirectional"))
      (node (ref "V_EXT") (pin "GNDBREAK") (pinfunction "GNDBREAK_GNDBREAK") (pintype "bidirectional"))
    )
    (net (code "53") (name "V+") (class "Default")
      (node (ref "A0[28]") (pin "1") (pinfunction "1_1") (pintype "passive"))
      (node (ref "A1[29]") (pin "1") (pinfunction "1_1") (pintype "passive"))
      (node (ref "A2[30]") (pin "1") (pinfunction "1_1") (pintype "passive"))
      (node (ref "A3[31]") (pin "1") (pinfunction "1_1") (pintype "passive"))
      (node (ref "A4[32]") (pin "1") (pinfunction "1_1") (pintype "passive"))
      (node (ref "A5[33]") (pin "1") (pinfunction "1_1") (pintype "passive"))
      (node (ref "A6[34]") (pin "1") (pinfunction "1_1") (pintype "passive"))
      (node (ref "A7[35]") (pin "1") (pinfunction "1_1") (pintype "passive"))
      (node (ref "B0[20]") (pin "1") (pinfunction "1_1") (pintype "passive"))
      (node (ref "B1[21]") (pin "1") (pinfunction "1_1") (pintype "passive"))
      (node (ref "B2[22]") (pin "1") (pinfunction "1_1") (pintype "passive"))
      (node (ref "B3[23]") (pin "1") (pinfunction "1_1") (pintype "passive"))
      (node (ref "B4[23]") (pin "1") (pinfunction "1_1") (pintype "passive"))
      (node (ref "B5[24]") (pin "1") (pinfunction "1_1") (pintype "passive"))
      (node (ref "B6[26]") (pin "1") (pinfunction "1_1") (pintype "passive"))
      (node (ref "B7[27]") (pin "1") (pinfunction "1_1") (pintype "passive"))
      (node (ref "C0[10]") (pin "1") (pinfunction "1_1") (pintype "passive"))
      (node (ref "C1[11]") (pin "1") (pinfunction "1_1") (pintype "passive"))
      (node (ref "C2[12]") (pin "1") (pinfunction "1_1") (pintype "passive"))
      (node (ref "C3[13]") (pin "1") (pinfunction "1_1") (pintype "passive"))
      (node (ref "C4[14]") (pin "1") (pinfunction "1_1") (pintype "passive"))
      (node (ref "C5[15]") (pin "1") (pinfunction "1_1") (pintype "passive"))
      (node (ref "C6[16]") (pin "1") (pinfunction "1_1") (pintype "passive"))
      (node (ref "C7[17]") (pin "1") (pinfunction "1_1") (pintype "passive"))
      (node (ref "D0[0]") (pin "1") (pinfunction "1_1") (pintype "passive"))
      (node (ref "D1[1]") (pin "1") (pinfunction "1_1") (pintype "passive"))
      (node (ref "D2[2]") (pin "1") (pinfunction "1_1") (pintype "passive"))
      (node (ref "D3[3]") (pin "1") (pinfunction "1_1") (pintype "passive"))
      (node (ref "D4[22]") (pin "1") (pinfunction "1_1") (pintype "passive"))
      (node (ref "D4[4]") (pin "1") (pinfunction "1_1") (pintype "passive"))
      (node (ref "D5[23]") (pin "1") (pinfunction "1_1") (pintype "passive"))
      (node (ref "D5[5]") (pin "1") (pinfunction "1_1") (pintype "passive"))
      (node (ref "D6[6]") (pin "1") (pinfunction "1_1") (pintype "passive"))
      (node (ref "D7[12]") (pin "1") (pinfunction "1_1") (pintype "passive"))
      (node (ref "D7[7]") (pin "1") (pinfunction "1_1") (pintype "passive"))
      (node (ref "E0[8]") (pin "1") (pinfunction "1_1") (pintype "passive"))
      (node (ref "E1[9]") (pin "1") (pinfunction "1_1") (pintype "passive"))
      (node (ref "E4[36]") (pin "1") (pinfunction "1_1") (pintype "passive"))
      (node (ref "E5[37]") (pin "1") (pinfunction "1_1") (pintype "passive"))
      (node (ref "E6[18]") (pin "1") (pinfunction "1_1") (pintype "passive"))
      (node (ref "E6[24]") (pin "1") (pinfunction "1_1") (pintype "passive"))
      (node (ref "E7[19]") (pin "1") (pinfunction "1_1") (pintype "passive"))
      (node (ref "F0[38]") (pin "1") (pinfunction "1_1") (pintype "passive"))
      (node (ref "F1[39]") (pin "1") (pinfunction "1_1") (pintype "passive"))
      (node (ref "F2[40]") (pin "1") (pinfunction "1_1") (pintype "passive"))
      (node (ref "F3[41]") (pin "1") (pinfunction "1_1") (pintype "passive"))
      (node (ref "F4[42]") (pin "1") (pinfunction "1_1") (pintype "passive"))
      (node (ref "F5[43]") (pin "1") (pinfunction "1_1") (pintype "passive"))
      (node (ref "F6[44]") (pin "1") (pinfunction "1_1") (pintype "passive"))
      (node (ref "F7[45]") (pin "1") (pinfunction "1_1") (pintype "passive"))
      (node (ref "TEENSY-POWER") (pin "2") (pinfunction "2_2") (pintype "passive"))
      (node (ref "VCC_SELECT") (pin "3") (pinfunction "3_3") (pintype "passive"))
      (node (ref "V_EXT") (pin "PWR") (pinfunction "PWR_PWR") (pintype "bidirectional"))
    )
    (net (code "54") (name "VCC") (class "Default")
      (node (ref "I2C_TEENSY") (pin "2") (pinfunction "2_2") (pintype "passive"))
      (node (ref "I2C_TEENSY++") (pin "2") (pinfunction "2_2") (pintype "passive"))
      (node (ref "I2C_TEENSY1") (pin "2") (pinfunction "2_2") (pintype "passive"))
      (node (ref "I2C_TEENSY2") (pin "2") (pinfunction "2_2") (pintype "passive"))
      (node (ref "I2C_TEENSYPP1") (pin "2") (pinfunction "2_2") (pintype "passive"))
      (node (ref "I2C_TEENSYPP2") (pin "2") (pinfunction "2_2") (pintype "passive"))
      (node (ref "TEENSY-POWER") (pin "1") (pinfunction "1_1") (pintype "passive"))
      (node (ref "TEENSY2/++") (pin "VCC") (pinfunction "VCC_VCC") (pintype "power_in"))
      (node (ref "VCC_SELECT") (pin "1") (pinfunction "1_1") (pintype "passive"))
    )
    (net (code "55") (name "unconnected-(TEENSY2/++-AREF_12,AREF_D6-PadAREF_D6)") (class "Default")
      (node (ref "TEENSY2/++") (pin "AREF_D6") (pinfunction "AREF_12,AREF_D6_AREF_D6") (pintype "input"))
    )
    (net (code "56") (name "unconnected-(TEENSY2/++-PadGND2_)") (class "Default")
      (node (ref "TEENSY2/++") (pin "GND2_") (pinfunction "GND2__GND2_") (pintype "power_in"))
    )
    (net (code "57") (name "unconnected-(TEENSY2/++-PadRST_)") (class "Default")
      (node (ref "TEENSY2/++") (pin "RST_") (pinfunction "RST__RST_") (pintype "input"))
    )
    (net (code "58") (name "unconnected-(TEENSY2/++-PadVCC1_)") (class "Default")
      (node (ref "TEENSY2/++") (pin "VCC1_") (pinfunction "VCC1__VCC1_") (pintype "power_in"))
    )
    (net (code "59") (name "unconnected-(TEENSY2/++-Pad_GND1)") (class "Default")
      (node (ref "TEENSY2/++") (pin "_GND1") (pinfunction "_GND1__GND1") (pintype "bidirectional"))
    )
    (net (code "60") (name "unconnected-(TEENSY2/++-Pad_RST)") (class "Default")
      (node (ref "TEENSY2/++") (pin "_RST") (pinfunction "_RST__RST") (pintype "bidirectional"))
    )
    (net (code "61") (name "unconnected-(TEENSY2/++-_5V2-Pad_VCC1)") (class "Default")
      (node (ref "TEENSY2/++") (pin "_VCC1") (pinfunction "_5V2__VCC1") (pintype "bidirectional"))
    )
    (net (code "62") (name "unconnected-(TEENSY2/++-_AREF,_F5-Pad_AREF)") (class "Default")
      (node (ref "TEENSY2/++") (pin "_AREF") (pinfunction "_AREF,_F5__AREF") (pintype "bidirectional"))
    )
  )
)
